# BLE-Board-v2.net
KiCad netlist of a schematic drawn in EAGLE
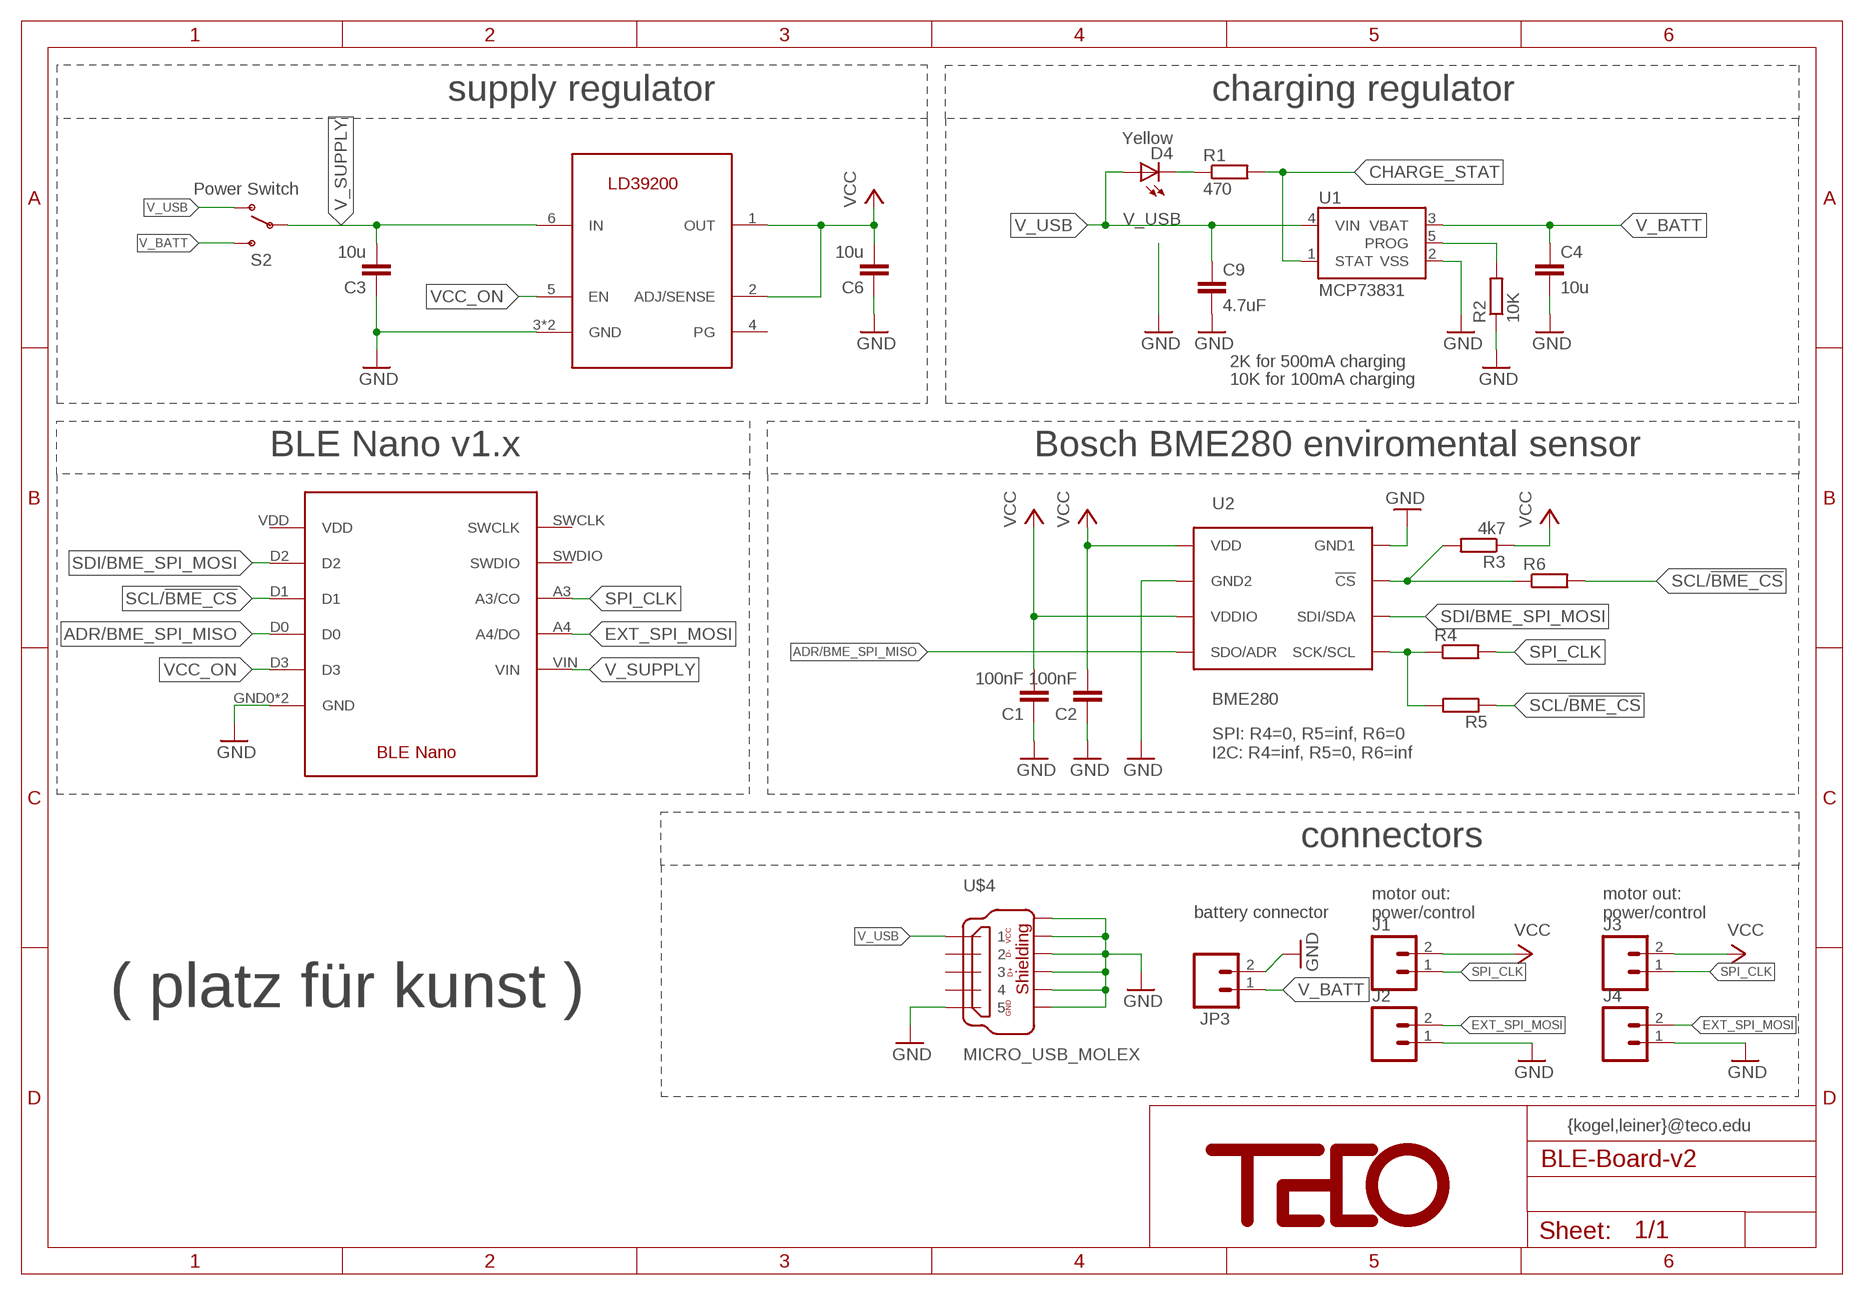
[diagram p0: schematic, sheet 1]

(export (version "E")
  (design (tool "Eeschema 10.0.6"))
  (components
    (comp (ref "C1")
      (value "100nF")
      (footprint "eagle-import:C0603K")
      (libsource (lib "eagle-import") (part "C-EUC0603K"))
    )
    (comp (ref "C2")
      (value "100nF")
      (footprint "eagle-import:C0603K")
      (libsource (lib "eagle-import") (part "C-EUC0603K"))
    )
    (comp (ref "C3")
      (value "10u")
      (footprint "eagle-import:C0603K")
      (libsource (lib "eagle-import") (part "C-EUC0603K"))
    )
    (comp (ref "C4")
      (value "10u")
      (footprint "eagle-import:C0603K")
      (libsource (lib "eagle-import") (part "C-EUC0603K"))
    )
    (comp (ref "C6")
      (value "10u")
      (footprint "eagle-import:C0603K")
      (libsource (lib "eagle-import") (part "C-EUC0603K"))
    )
    (comp (ref "C9")
      (value "4.7uF")
      (footprint "eagle-import:C0603K")
      (libsource (lib "eagle-import") (part "C-EUC0603K"))
    )
    (comp (ref "D4")
      (value "Yellow")
      (footprint "eagle-import:LED-0603")
      (libsource (lib "eagle-import") (part "LED0603"))
    )
    (comp (ref "J1")
      (value "M02PTH")
      (footprint "eagle-import:1X02")
      (libsource (lib "eagle-import") (part "SparkFun-Connectors_M02PTH"))
    )
    (comp (ref "J2")
      (value "M02PTH")
      (footprint "eagle-import:1X02")
      (libsource (lib "eagle-import") (part "SparkFun-Connectors_M02PTH"))
    )
    (comp (ref "J3")
      (value "M02PTH")
      (footprint "eagle-import:1X02")
      (libsource (lib "eagle-import") (part "SparkFun-Connectors_M02PTH"))
    )
    (comp (ref "J4")
      (value "M02PTH")
      (footprint "eagle-import:1X02")
      (libsource (lib "eagle-import") (part "SparkFun-Connectors_M02PTH"))
    )
    (comp (ref "JP3")
      (value "M02-JST-2MM-SMT")
      (footprint "eagle-import:JST-2-SMD")
      (libsource (lib "eagle-import") (part "M02-JST-2MM-SMT"))
    )
    (comp (ref "R1")
      (value "470")
      (footprint "eagle-import:R0402")
      (libsource (lib "eagle-import") (part "R-EU_R0402"))
    )
    (comp (ref "R2")
      (value "10K")
      (footprint "eagle-import:R0402")
      (libsource (lib "eagle-import") (part "R-EU_R0402"))
    )
    (comp (ref "R3")
      (value "4k7")
      (footprint "eagle-import:R0402")
      (libsource (lib "eagle-import") (part "R-EU_R0402"))
    )
    (comp (ref "R4")
      (value "R-EU_R0201")
      (footprint "eagle-import:R0201")
      (libsource (lib "eagle-import") (part "R-EU_R0201"))
    )
    (comp (ref "R5")
      (value "R-EU_R0201")
      (footprint "eagle-import:R0201")
      (libsource (lib "eagle-import") (part "R-EU_R0201"))
    )
    (comp (ref "R6")
      (value "R-EU_R0201")
      (footprint "eagle-import:R0201")
      (libsource (lib "eagle-import") (part "R-EU_R0201"))
    )
    (comp (ref "S2")
      (value "Power Switch")
      (footprint "eagle-import:AYZ0202")
      (libsource (lib "eagle-import") (part "SWITCH-SPSTSMD"))
    )
    (comp (ref "U$1")
      (value "BLE-NANO")
      (footprint "eagle-import:BLE-NANO")
      (libsource (lib "eagle-import") (part "BLE-NANO"))
    )
    (comp (ref "U$2")
      (value "LD39200DNF6")
      (footprint "eagle-import:DFN6-3X3")
      (libsource (lib "eagle-import") (part "LD39200DNF6"))
    )
    (comp (ref "U$3")
      (value "TECO-LOGO-BIG")
      (footprint "eagle-import:TECO-LOGO-BIG")
      (libsource (lib "eagle-import") (part "TECO-LOGO-BIG"))
    )
    (comp (ref "U$4")
      (value "MICRO_USB_MOLEX")
      (footprint "eagle-import:MICRO_USB_MOLEX")
      (libsource (lib "eagle-import") (part "MICRO_USB_MOLEX"))
    )
    (comp (ref "U1")
      (value "MCP73831")
      (footprint "eagle-import:SOT23-5")
      (libsource (lib "eagle-import") (part "MCP73831"))
    )
    (comp (ref "U2")
      (value "BME280")
      (footprint "eagle-import:BME280_LGA")
      (libsource (lib "eagle-import") (part "BME280"))
    )
  )
  (nets
    (net (code "1") (name "/SCL{slash}~{BME_CS}") (class "Default")
      (node (ref "R5") (pin "1") (pinfunction "1_1") (pintype "passive"))
      (node (ref "R6") (pin "2") (pinfunction "2_2") (pintype "passive"))
      (node (ref "U$1") (pin "D1") (pinfunction "D1_D1") (pintype "bidirectional"))
    )
    (net (code "2") (name "ADR{slash}BME_SPI_MISO") (class "Default")
      (node (ref "U$1") (pin "D0") (pinfunction "D0_D0") (pintype "bidirectional"))
      (node (ref "U2") (pin "P$5") (pinfunction "SDO/ADR_P$5") (pintype "bidirectional"))
    )
    (net (code "3") (name "CHARGE_STAT") (class "Default")
      (node (ref "R1") (pin "2") (pinfunction "2_2") (pintype "passive"))
      (node (ref "U1") (pin "1") (pinfunction "STAT_1") (pintype "output"))
    )
    (net (code "4") (name "EXT_SPI_MOSI") (class "Default")
      (node (ref "J2") (pin "2") (pinfunction "2_2") (pintype "passive"))
      (node (ref "J4") (pin "2") (pinfunction "2_2") (pintype "passive"))
      (node (ref "U$1") (pin "A4") (pinfunction "A4/DO_A4") (pintype "bidirectional"))
    )
    (net (code "5") (name "GND") (class "Default")
      (node (ref "C1") (pin "1") (pinfunction "1_1") (pintype "passive"))
      (node (ref "C2") (pin "1") (pinfunction "1_1") (pintype "passive"))
      (node (ref "C3") (pin "1") (pinfunction "1_1") (pintype "passive"))
      (node (ref "C4") (pin "2") (pinfunction "2_2") (pintype "passive"))
      (node (ref "C6") (pin "1") (pinfunction "1_1") (pintype "passive"))
      (node (ref "C9") (pin "2") (pinfunction "2_2") (pintype "passive"))
      (node (ref "J2") (pin "1") (pinfunction "1_1") (pintype "passive"))
      (node (ref "J4") (pin "1") (pinfunction "1_1") (pintype "passive"))
      (node (ref "JP3") (pin "2") (pinfunction "2_2") (pintype "passive"))
      (node (ref "R2") (pin "1") (pinfunction "1_1") (pintype "passive"))
      (node (ref "U$1") (pin "GND0") (pinfunction "GND_GND0") (pintype "bidirectional"))
      (node (ref "U$1") (pin "GND1") (pinfunction "GND_GND1") (pintype "bidirectional"))
      (node (ref "U$2") (pin "3") (pinfunction "GND_3") (pintype "power_in"))
      (node (ref "U$2") (pin "EXP") (pinfunction "GND_EXP") (pintype "power_in"))
      (node (ref "U$4") (pin "5") (pinfunction "5_5") (pintype "input"))
      (node (ref "U$4") (pin "SHIELD@1") (pinfunction "P$1_SHIELD@1") (pintype "bidirectional"))
      (node (ref "U$4") (pin "SHIELD@2") (pinfunction "P$2_SHIELD@2") (pintype "bidirectional"))
      (node (ref "U$4") (pin "SHIELD@3") (pinfunction "P$3_SHIELD@3") (pintype "bidirectional"))
      (node (ref "U$4") (pin "SHIELD@4") (pinfunction "P$4_SHIELD@4") (pintype "bidirectional"))
      (node (ref "U$4") (pin "SHIELD@5") (pinfunction "P$5_SHIELD@5") (pintype "bidirectional"))
      (node (ref "U$4") (pin "SHIELD@6") (pinfunction "P$6_SHIELD@6") (pintype "bidirectional"))
      (node (ref "U1") (pin "2") (pinfunction "VSS_2") (pintype "power_in"))
      (node (ref "U2") (pin "P$1") (pinfunction "GND1_P$1") (pintype "bidirectional"))
      (node (ref "U2") (pin "P$7") (pinfunction "GND2_P$7") (pintype "bidirectional"))
    )
    (net (code "6") (name "Net-(D4-PadC)") (class "Default")
      (node (ref "D4") (pin "C") (pinfunction "C_C") (pintype "passive"))
      (node (ref "R1") (pin "1") (pinfunction "1_1") (pintype "passive"))
    )
    (net (code "7") (name "Net-(U1-PROG)") (class "Default")
      (node (ref "R2") (pin "2") (pinfunction "2_2") (pintype "passive"))
      (node (ref "U1") (pin "5") (pinfunction "PROG_5") (pintype "input"))
    )
    (net (code "8") (name "Net-(U2-SCK{slash}SCL)") (class "Default")
      (node (ref "R4") (pin "1") (pinfunction "1_1") (pintype "passive"))
      (node (ref "R5") (pin "2") (pinfunction "2_2") (pintype "passive"))
      (node (ref "U2") (pin "P$4") (pinfunction "SCK/SCL_P$4") (pintype "bidirectional"))
    )
    (net (code "9") (name "Net-(U2-~{CS})") (class "Default")
      (node (ref "R3") (pin "2") (pinfunction "2_2") (pintype "passive"))
      (node (ref "R6") (pin "1") (pinfunction "1_1") (pintype "passive"))
      (node (ref "U2") (pin "P$2") (pinfunction "~{CS}_P$2") (pintype "bidirectional"))
    )
    (net (code "10") (name "SDI{slash}BME_SPI_MOSI") (class "Default")
      (node (ref "U$1") (pin "D2") (pinfunction "D2_D2") (pintype "bidirectional"))
      (node (ref "U2") (pin "P$3") (pinfunction "SDI/SDA_P$3") (pintype "bidirectional"))
    )
    (net (code "11") (name "SPI_CLK") (class "Default")
      (node (ref "J1") (pin "1") (pinfunction "1_1") (pintype "passive"))
      (node (ref "J3") (pin "1") (pinfunction "1_1") (pintype "passive"))
      (node (ref "R4") (pin "2") (pinfunction "2_2") (pintype "passive"))
      (node (ref "U$1") (pin "A3") (pinfunction "A3/CO_A3") (pintype "bidirectional"))
    )
    (net (code "12") (name "VCC") (class "Default")
      (node (ref "C1") (pin "2") (pinfunction "2_2") (pintype "passive"))
      (node (ref "C2") (pin "2") (pinfunction "2_2") (pintype "passive"))
      (node (ref "C6") (pin "2") (pinfunction "2_2") (pintype "passive"))
      (node (ref "J1") (pin "2") (pinfunction "2_2") (pintype "passive"))
      (node (ref "J3") (pin "2") (pinfunction "2_2") (pintype "passive"))
      (node (ref "R3") (pin "1") (pinfunction "1_1") (pintype "passive"))
      (node (ref "U$2") (pin "1") (pinfunction "OUT_1") (pintype "power_in"))
      (node (ref "U$2") (pin "2") (pinfunction "ADJ/SENSE_2") (pintype "bidirectional"))
      (node (ref "U2") (pin "P$6") (pinfunction "VDDIO_P$6") (pintype "bidirectional"))
      (node (ref "U2") (pin "P$8") (pinfunction "VDD_P$8") (pintype "bidirectional"))
    )
    (net (code "13") (name "VCC_ON") (class "Default")
      (node (ref "U$1") (pin "D3") (pinfunction "D3_D3") (pintype "bidirectional"))
      (node (ref "U$2") (pin "5") (pinfunction "EN_5") (pintype "input"))
    )
    (net (code "14") (name "V_BATT") (class "Default")
      (node (ref "C4") (pin "1") (pinfunction "1_1") (pintype "passive"))
      (node (ref "JP3") (pin "1") (pinfunction "1_1") (pintype "passive"))
      (node (ref "S2") (pin "3") (pinfunction "S_3") (pintype "passive"))
      (node (ref "U1") (pin "3") (pinfunction "VBAT_3") (pintype "power_in"))
    )
    (net (code "15") (name "V_SUPPLY") (class "Default")
      (node (ref "C3") (pin "2") (pinfunction "2_2") (pintype "passive"))
      (node (ref "S2") (pin "2") (pinfunction "P_2") (pintype "passive"))
      (node (ref "U$1") (pin "VIN") (pinfunction "VIN_VIN") (pintype "bidirectional"))
      (node (ref "U$2") (pin "6") (pinfunction "IN_6") (pintype "power_in"))
    )
    (net (code "16") (name "V_USB") (class "Default")
      (node (ref "C9") (pin "1") (pinfunction "1_1") (pintype "passive"))
      (node (ref "D4") (pin "A") (pinfunction "A_A") (pintype "passive"))
      (node (ref "S2") (pin "1") (pinfunction "O_1") (pintype "passive"))
      (node (ref "U$4") (pin "1") (pinfunction "1_1") (pintype "input"))
      (node (ref "U1") (pin "4") (pinfunction "VIN_4") (pintype "power_in"))
    )
    (net (code "17") (name "unconnected-(U$1-PadSWCLK)") (class "Default")
      (node (ref "U$1") (pin "SWCLK") (pinfunction "SWCLK_SWCLK") (pintype "bidirectional"))
    )
    (net (code "18") (name "unconnected-(U$1-PadSWDIO)") (class "Default")
      (node (ref "U$1") (pin "SWDIO") (pinfunction "SWDIO_SWDIO") (pintype "bidirectional"))
    )
    (net (code "19") (name "unconnected-(U$1-PadVDD)") (class "Default")
      (node (ref "U$1") (pin "VDD") (pinfunction "VDD_VDD") (pintype "bidirectional"))
    )
    (net (code "20") (name "unconnected-(U$2-PG-Pad4)") (class "Default")
      (node (ref "U$2") (pin "4") (pinfunction "PG_4") (pintype "input"))
    )
    (net (code "21") (name "unconnected-(U$4-Pad2)") (class "Default")
      (node (ref "U$4") (pin "2") (pinfunction "2_2") (pintype "input"))
    )
    (net (code "22") (name "unconnected-(U$4-Pad3)") (class "Default")
      (node (ref "U$4") (pin "3") (pinfunction "3_3") (pintype "input"))
    )
    (net (code "23") (name "unconnected-(U$4-Pad4)") (class "Default")
      (node (ref "U$4") (pin "4") (pinfunction "4_4") (pintype "input"))
    )
  )
)
